# amphenol_npa201_edgemount.net
KiCad netlist of a schematic drawn in EAGLE
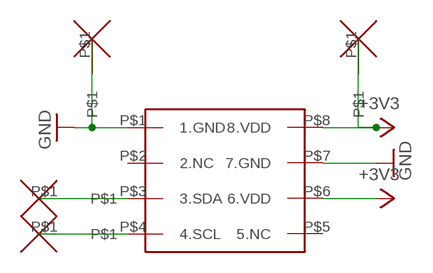
[diagram p0: schematic, sheet 1]

(export (version "E")
  (design (tool "Eeschema 10.0.6"))
  (components
    (comp (ref "U$1")
      (value "AMPHENOL_NPA201EDGEMOUNT")
      (footprint "eagle-import:AMPHENOL_NPA201_EDGEMOUNT")
      (libsource (lib "eagle-import") (part "AMPHENOL_NPA201EDGEMOUNT"))
    )
    (comp (ref "U$2")
      (value "WIREPADWIREPAD_0,5/0,3")
      (footprint "eagle-import:WIREPAD_0,5_0,3")
      (libsource (lib "eagle-import") (part "WIREPADWIREPAD_0,5/0,3"))
    )
    (comp (ref "U$3")
      (value "WIREPADWIREPAD_0,5/0,3")
      (footprint "eagle-import:WIREPAD_0,5_0,3")
      (libsource (lib "eagle-import") (part "WIREPADWIREPAD_0,5/0,3"))
    )
    (comp (ref "U$4")
      (value "WIREPADWIREPAD_0,5/0,3")
      (footprint "eagle-import:WIREPAD_0,5_0,3")
      (libsource (lib "eagle-import") (part "WIREPADWIREPAD_0,5/0,3"))
    )
    (comp (ref "U$5")
      (value "WIREPADWIREPAD_0,5/0,3")
      (footprint "eagle-import:WIREPAD_0,5_0,3")
      (libsource (lib "eagle-import") (part "WIREPADWIREPAD_0,5/0,3"))
    )
  )
  (nets
    (net (code "1") (name "+3V3") (class "Default")
      (node (ref "U$1") (pin "P$6") (pinfunction "6.VDD_P$6") (pintype "bidirectional"))
      (node (ref "U$1") (pin "P$8") (pinfunction "8.VDD_P$8") (pintype "bidirectional"))
      (node (ref "U$5") (pin "P$1") (pinfunction "P$1_P$1") (pintype "bidirectional"))
    )
    (net (code "2") (name "GND") (class "Default")
      (node (ref "U$1") (pin "P$1") (pinfunction "1.GND_P$1") (pintype "bidirectional"))
      (node (ref "U$1") (pin "P$7") (pinfunction "7.GND_P$7") (pintype "bidirectional"))
      (node (ref "U$4") (pin "P$1") (pinfunction "P$1_P$1") (pintype "bidirectional"))
    )
    (net (code "3") (name "Net-(U$1-3.SDA)") (class "Default")
      (node (ref "U$1") (pin "P$3") (pinfunction "3.SDA_P$3") (pintype "bidirectional"))
      (node (ref "U$2") (pin "P$1") (pinfunction "P$1_P$1") (pintype "bidirectional"))
    )
    (net (code "4") (name "Net-(U$1-4.SCL)") (class "Default")
      (node (ref "U$1") (pin "P$4") (pinfunction "4.SCL_P$4") (pintype "bidirectional"))
      (node (ref "U$3") (pin "P$1") (pinfunction "P$1_P$1") (pintype "bidirectional"))
    )
    (net (code "5") (name "unconnected-(U$1-2.NC-PadP$2)") (class "Default")
      (node (ref "U$1") (pin "P$2") (pinfunction "2.NC_P$2") (pintype "bidirectional"))
    )
    (net (code "6") (name "unconnected-(U$1-5.NC-PadP$5)") (class "Default")
      (node (ref "U$1") (pin "P$5") (pinfunction "5.NC_P$5") (pintype "bidirectional"))
    )
  )
)
